# Schematic.net
KiCad netlist of a schematic drawn in Altium Designer
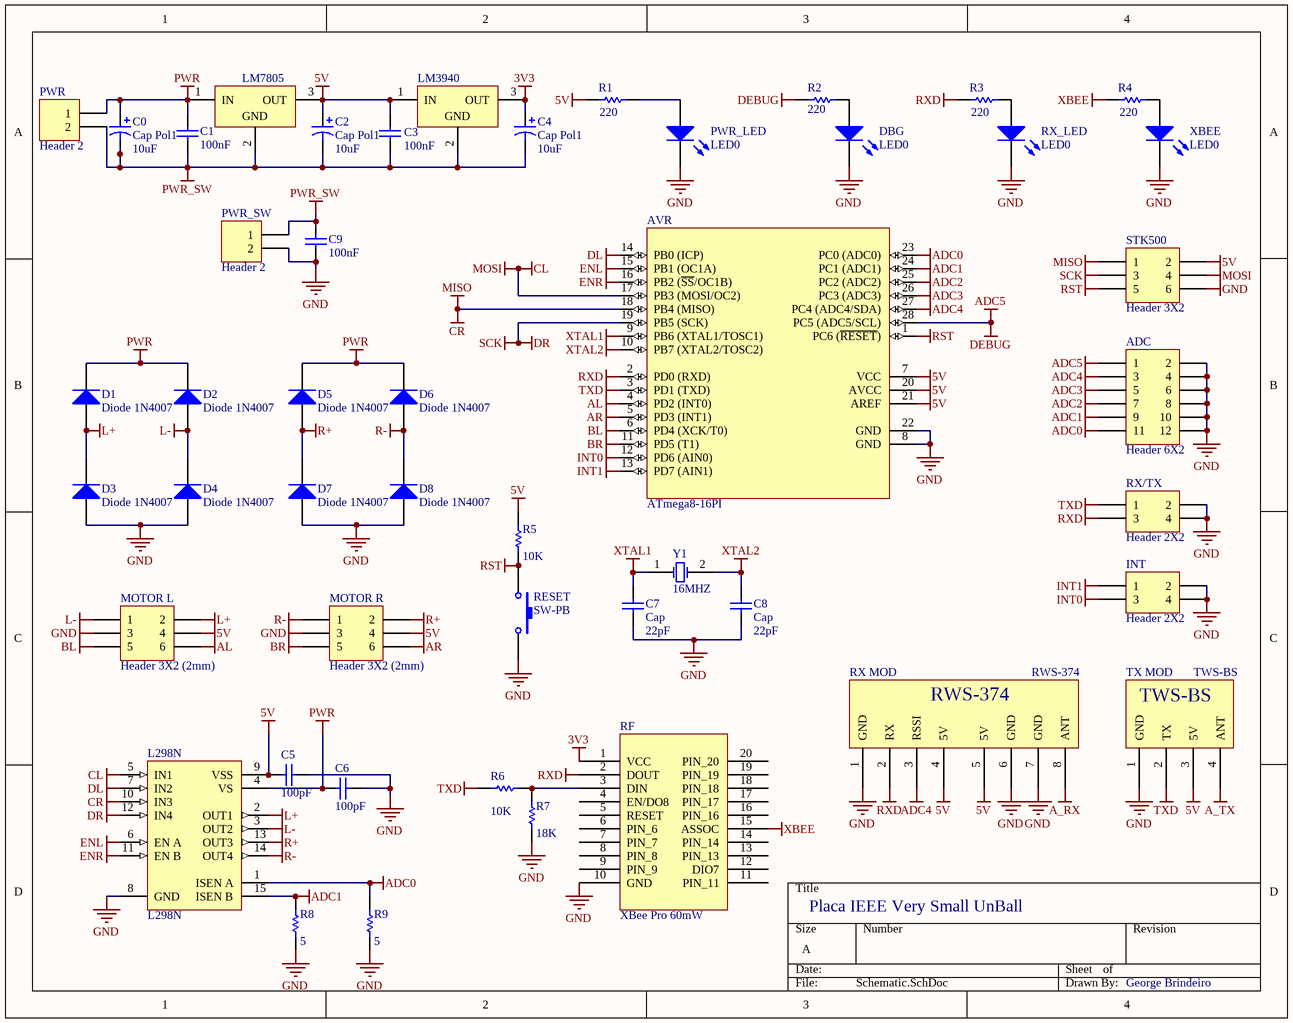
[diagram p0: Schematic.SchDoc]

(export (version "E")
  (design (tool "Eeschema 10.0.6"))
  (components
    (comp (ref "ADC")
      (value "Header 6X2")
      (footprint "HDR2X6")
      (description "Header, 6-Pin, Dual row")
      (fields (field (name "PUBLISHER") "Altium Limited"))
      (libsource (lib "Miscellaneous Connectors") (part "Header 6X2"))
    )
    (comp (ref "AVR")
      (value "ATmega8-16PI")
      (footprint "28P3")
      (description "8-Bit AVR Microcontroller with 8K Bytes of In-System Programmable Flash Memory")
      (fields (field (name "PUBLISHER") "Altium Limited"))
      (libsource (lib "Atmel Microcontroller 8-Bit AVR") (part "ATmega8-16PI"))
    )
    (comp (ref "C0")
      (value "Cap Pol1")
      (footprint "B")
      (description "Polarized Capacitor (Radial)")
      (fields (field (name "ALTIUM_VALUE") "10uF") (field (name "PUBLISHER") "Altium Limited"))
      (libsource (lib "Miscellaneous Devices") (part "Cap Pol1"))
    )
    (comp (ref "C1")
      (value "100nF")
      (footprint "C_NANO_HOLES")
      (description "Capacitor")
      (fields (field (name "Comment") "Cap") (field (name "PUBLISHER") "Altium Limited"))
      (libsource (lib "Miscellaneous Devices") (part "Cap"))
    )
    (comp (ref "C2")
      (value "Cap Pol1")
      (footprint "B")
      (description "Polarized Capacitor (Radial)")
      (fields (field (name "ALTIUM_VALUE") "10uF") (field (name "PUBLISHER") "Altium Limited"))
      (libsource (lib "Miscellaneous Devices") (part "Cap Pol1"))
    )
    (comp (ref "C3")
      (value "100nF")
      (footprint "C_NANO_HOLES")
      (description "Capacitor")
      (fields (field (name "Comment") "Cap") (field (name "PUBLISHER") "Altium Limited"))
      (libsource (lib "Miscellaneous Devices") (part "Cap"))
    )
    (comp (ref "C4")
      (value "Cap Pol1")
      (footprint "B")
      (description "Polarized Capacitor (Radial)")
      (fields (field (name "ALTIUM_VALUE") "10uF") (field (name "PUBLISHER") "Altium Limited"))
      (libsource (lib "Miscellaneous Devices") (part "Cap Pol1"))
    )
    (comp (ref "C5")
      (value "100pF")
      (footprint "C_NANO_HOLES")
      (description "Capacitor")
      (fields (field (name "Comment") "Cap") (field (name "PUBLISHER") "Altium Limited"))
      (libsource (lib "Miscellaneous Devices") (part "Cap"))
    )
    (comp (ref "C6")
      (value "100pF")
      (footprint "C_NANO_HOLES")
      (description "Capacitor")
      (fields (field (name "Comment") "Cap") (field (name "PUBLISHER") "Altium Limited"))
      (libsource (lib "Miscellaneous Devices") (part "Cap"))
    )
    (comp (ref "C7")
      (value "Cap")
      (footprint "C_NANO_HOLES")
      (description "Capacitor")
      (fields (field (name "ALTIUM_VALUE") "22pF") (field (name "PUBLISHER") "Altium Limited"))
      (libsource (lib "Miscellaneous Devices") (part "Cap"))
    )
    (comp (ref "C8")
      (value "Cap")
      (footprint "C_NANO_HOLES")
      (description "Capacitor")
      (fields (field (name "ALTIUM_VALUE") "22pF") (field (name "PUBLISHER") "Altium Limited"))
      (libsource (lib "Miscellaneous Devices") (part "Cap"))
    )
    (comp (ref "C9")
      (value "100nF")
      (footprint "C_NANO_HOLES")
      (description "Capacitor")
      (fields (field (name "Comment") "Cap") (field (name "PUBLISHER") "Altium Limited"))
      (libsource (lib "Miscellaneous Devices") (part "Cap"))
    )
    (comp (ref "D1")
      (value "Diode 1N4007")
      (footprint "DO-41")
      (description "1 Amp General Purpose Rectifier")
      (fields (field (name "PUBLISHER") "Altium Limited"))
      (libsource (lib "Miscellaneous Devices") (part "Diode 1N4007"))
    )
    (comp (ref "D2")
      (value "Diode 1N4007")
      (footprint "DO-41")
      (description "1 Amp General Purpose Rectifier")
      (fields (field (name "PUBLISHER") "Altium Limited"))
      (libsource (lib "Miscellaneous Devices") (part "Diode 1N4007"))
    )
    (comp (ref "D3")
      (value "Diode 1N4007")
      (footprint "DO-41")
      (description "1 Amp General Purpose Rectifier")
      (fields (field (name "PUBLISHER") "Altium Limited"))
      (libsource (lib "Miscellaneous Devices") (part "Diode 1N4007"))
    )
    (comp (ref "D4")
      (value "Diode 1N4007")
      (footprint "DO-41")
      (description "1 Amp General Purpose Rectifier")
      (fields (field (name "PUBLISHER") "Altium Limited"))
      (libsource (lib "Miscellaneous Devices") (part "Diode 1N4007"))
    )
    (comp (ref "D5")
      (value "Diode 1N4007")
      (footprint "DO-41")
      (description "1 Amp General Purpose Rectifier")
      (fields (field (name "PUBLISHER") "Altium Limited"))
      (libsource (lib "Miscellaneous Devices") (part "Diode 1N4007"))
    )
    (comp (ref "D6")
      (value "Diode 1N4007")
      (footprint "DO-41")
      (description "1 Amp General Purpose Rectifier")
      (fields (field (name "PUBLISHER") "Altium Limited"))
      (libsource (lib "Miscellaneous Devices") (part "Diode 1N4007"))
    )
    (comp (ref "D7")
      (value "Diode 1N4007")
      (footprint "DO-41")
      (description "1 Amp General Purpose Rectifier")
      (fields (field (name "PUBLISHER") "Altium Limited"))
      (libsource (lib "Miscellaneous Devices") (part "Diode 1N4007"))
    )
    (comp (ref "D8")
      (value "Diode 1N4007")
      (footprint "DO-41")
      (description "1 Amp General Purpose Rectifier")
      (fields (field (name "PUBLISHER") "Altium Limited"))
      (libsource (lib "Miscellaneous Devices") (part "Diode 1N4007"))
    )
    (comp (ref "DBG")
      (value "LED0")
      (footprint "B")
      (description "Typical INFRARED GaAs LED")
      (fields (field (name "PUBLISHER") "Altium Limited"))
      (libsource (lib "Miscellaneous Devices") (part "LED0"))
    )
    (comp (ref "INT")
      (value "Header 2X2")
      (footprint "HDR2X2")
      (description "Header, 2-Pin, Dual row")
      (fields (field (name "PUBLISHER") "Altium Limited"))
      (libsource (lib "Miscellaneous Connectors") (part "Header 2X2"))
    )
    (comp (ref "L298N")
      (value "L298N")
      (footprint "Multiwatt15V")
      (description "Dual Full Bridge Driver")
      (fields (field (name "PUBLISHER") "Altium Limited"))
      (libsource (lib "ST Interface DC Motor Controller") (part "L298N"))
    )
    (comp (ref "LM3940")
      (value "LM3940IT-3.3")
      (footprint "T03B")
      (description "1A Low Dropout Regulator for 5V to 3.3V Conversion")
      (fields
        (field (name "MANUFACTURER") "National Semiconductor")
        (field (name "DIGIKEYPARTNUMBER") "LM3940IT-3.3-ND")
        (field (name "PUBLISHER") "Altium Limited")
      )
      (libsource (lib "NSC LDO") (part "LM3940IT-3.3"))
    )
    (comp (ref "LM7805")
      (value "µA7805CKC")
      (footprint "KC03")
      (description "Positive-Voltage Regulator")
      (fields (field (name "PUBLISHER") "Altium Limited"))
      (libsource (lib "TI Power Mgt Voltage Regulator") (part "µA7805CKC"))
    )
    (comp (ref "MOTOR L")
      (value "Header 3X2 (2mm)")
      (footprint "HDR2x3_2MM")
      (description "Header, 3-Pin, Dual row")
      (fields (field (name "PUBLISHER") "Altium Limited"))
      (libsource (lib "Miscellaneous Connectors") (part "Header 3X2"))
    )
    (comp (ref "MOTOR R")
      (value "Header 3X2 (2mm)")
      (footprint "HDR2x3_2MM")
      (description "Header, 3-Pin, Dual row")
      (fields (field (name "PUBLISHER") "Altium Limited"))
      (libsource (lib "Miscellaneous Connectors") (part "Header 3X2"))
    )
    (comp (ref "PWR")
      (value "Header 2")
      (footprint "HDR1X2")
      (description "Header, 2-Pin")
      (fields (field (name "PUBLISHER") "Altium Limited"))
      (libsource (lib "Miscellaneous Connectors") (part "Header 2"))
    )
    (comp (ref "PWR_LED")
      (value "LED0")
      (footprint "B")
      (description "Typical INFRARED GaAs LED")
      (fields (field (name "PUBLISHER") "Altium Limited"))
      (libsource (lib "Miscellaneous Devices") (part "LED0"))
    )
    (comp (ref "PWR_SW")
      (value "Header 2")
      (footprint "HDR1X2")
      (description "Header, 2-Pin")
      (fields (field (name "PUBLISHER") "Altium Limited"))
      (libsource (lib "Miscellaneous Connectors") (part "Header 2"))
    )
    (comp (ref "R1")
      (value "220")
      (footprint "AXIAL-0.3")
      (description "Resistor")
      (fields (field (name "PUBLISHER") "Altium Limited"))
      (libsource (lib "Miscellaneous Devices") (part "Res1"))
    )
    (comp (ref "R2")
      (value "220")
      (footprint "AXIAL-0.3")
      (description "Resistor")
      (fields (field (name "PUBLISHER") "Altium Limited"))
      (libsource (lib "Miscellaneous Devices") (part "Res1"))
    )
    (comp (ref "R3")
      (value "220")
      (footprint "AXIAL-0.3")
      (description "Resistor")
      (fields (field (name "PUBLISHER") "Altium Limited"))
      (libsource (lib "Miscellaneous Devices") (part "Res1"))
    )
    (comp (ref "R4")
      (value "220")
      (footprint "AXIAL-0.3")
      (description "Resistor")
      (fields (field (name "PUBLISHER") "Altium Limited"))
      (libsource (lib "Miscellaneous Devices") (part "Res1"))
    )
    (comp (ref "R5")
      (value "10K")
      (footprint "AXIAL-0.3")
      (description "Resistor")
      (fields (field (name "PUBLISHER") "Altium Limited"))
      (libsource (lib "Miscellaneous Devices") (part "Res1"))
    )
    (comp (ref "R6")
      (value "10K")
      (footprint "AXIAL-0.3")
      (description "Resistor")
      (fields (field (name "PUBLISHER") "Altium Limited"))
      (libsource (lib "Miscellaneous Devices") (part "Res1"))
    )
    (comp (ref "R7")
      (value "18K")
      (footprint "AXIAL-0.3")
      (description "Resistor")
      (fields (field (name "PUBLISHER") "Altium Limited"))
      (libsource (lib "Miscellaneous Devices") (part "Res1"))
    )
    (comp (ref "R8")
      (value "5")
      (footprint "AXIAL-0.3")
      (description "Resistor")
      (fields (field (name "PUBLISHER") "Altium Limited"))
      (libsource (lib "Miscellaneous Devices") (part "Res1"))
    )
    (comp (ref "R9")
      (value "5")
      (footprint "AXIAL-0.3")
      (description "Resistor")
      (fields (field (name "PUBLISHER") "Altium Limited"))
      (libsource (lib "Miscellaneous Devices") (part "Res1"))
    )
    (comp (ref "RESET")
      (value "SW-PB")
      (footprint "PUSHBUTTON")
      (description "Switch")
      (fields (field (name "PUBLISHER") "Altium Limited"))
      (libsource (lib "Miscellaneous Devices") (part "SW-PB"))
    )
    (comp (ref "RF") (value "XBee Pro 60mW") (footprint "XBEE_PRO") (libsource (lib "Schlib") (part "XBee")))
    (comp (ref "RX MOD")
      (value "RWS-374")
      (footprint "RWS-374")
      (description "Receptor RF Soldafria")
      (libsource (lib "Schlib") (part "RWS-374"))
    )
    (comp (ref "RX/TX")
      (value "Header 2X2")
      (footprint "HDR2X2")
      (description "Header, 2-Pin, Dual row")
      (fields (field (name "PUBLISHER") "Altium Limited"))
      (libsource (lib "Miscellaneous Connectors") (part "Header 2X2"))
    )
    (comp (ref "RX_LED")
      (value "LED0")
      (footprint "B")
      (description "Typical INFRARED GaAs LED")
      (fields (field (name "PUBLISHER") "Altium Limited"))
      (libsource (lib "Miscellaneous Devices") (part "LED0"))
    )
    (comp (ref "STK500")
      (value "Header 3X2")
      (footprint "HDR2X3")
      (description "Header, 3-Pin, Dual row")
      (fields (field (name "PUBLISHER") "Altium Limited"))
      (libsource (lib "Miscellaneous Connectors") (part "Header 3X2"))
    )
    (comp (ref "TX MOD")
      (value "TWS-BS")
      (footprint "TWS-BS")
      (description "Transmissor RF Soldafria")
      (libsource (lib "Schlib") (part "TWS-BS"))
    )
    (comp (ref "XBEE")
      (value "LED0")
      (footprint "B")
      (description "Typical INFRARED GaAs LED")
      (fields (field (name "PUBLISHER") "Altium Limited"))
      (libsource (lib "Miscellaneous Devices") (part "LED0"))
    )
    (comp (ref "Y1")
      (value "16MHZ")
      (footprint "BCY-W2/E4.7")
      (description "Crystal Oscillator")
      (fields (field (name "PUBLISHER") "Altium Limited"))
      (libsource (lib "ECS Crystal Oscillator") (part "ECS-120-32-1"))
    )
  )
  (nets
    (net (code "1") (name "3V3") (class "Default")
      (node (ref "C4") (pin "1") (pinfunction "1_1") (pintype "passive"))
      (node (ref "LM3940") (pin "3") (pinfunction "OUT_3") (pintype "power_in"))
      (node (ref "RF") (pin "1") (pinfunction "VCC_1") (pintype "passive"))
    )
    (net (code "2") (name "5V") (class "Default")
      (node (ref "AVR") (pin "20") (pinfunction "AVCC_20") (pintype "power_in"))
      (node (ref "AVR") (pin "21") (pinfunction "AREF_21") (pintype "passive"))
      (node (ref "AVR") (pin "7") (pinfunction "VCC_7") (pintype "power_in"))
      (node (ref "C2") (pin "1") (pinfunction "1_1") (pintype "passive"))
      (node (ref "C3") (pin "1") (pinfunction "1_1") (pintype "passive"))
      (node (ref "C5") (pin "1") (pinfunction "1_1") (pintype "passive"))
      (node (ref "L298N") (pin "9") (pinfunction "VSS_9") (pintype "power_in"))
      (node (ref "LM3940") (pin "1") (pinfunction "IN_1") (pintype "power_in"))
      (node (ref "LM7805") (pin "3") (pinfunction "OUT_3") (pintype "power_in"))
      (node (ref "MOTOR L") (pin "4") (pinfunction "4_4") (pintype "passive"))
      (node (ref "MOTOR R") (pin "4") (pinfunction "4_4") (pintype "passive"))
      (node (ref "R1") (pin "1") (pinfunction "1_1") (pintype "passive"))
      (node (ref "R5") (pin "2") (pinfunction "2_2") (pintype "passive"))
      (node (ref "RX MOD") (pin "4") (pinfunction "5V_4") (pintype "passive"))
      (node (ref "RX MOD") (pin "5") (pinfunction "5V_5") (pintype "passive"))
      (node (ref "STK500") (pin "2") (pinfunction "2_2") (pintype "passive"))
      (node (ref "TX MOD") (pin "3") (pinfunction "5V_3") (pintype "passive"))
    )
    (net (code "3") (name "ADC0") (class "Default")
      (node (ref "ADC") (pin "11") (pinfunction "11_11") (pintype "passive"))
      (node (ref "AVR") (pin "23") (pinfunction "PC0_(ADC0)_23") (pintype "bidirectional"))
      (node (ref "L298N") (pin "1") (pinfunction "ISEN_A_1") (pintype "passive"))
      (node (ref "R9") (pin "2") (pinfunction "2_2") (pintype "passive"))
    )
    (net (code "4") (name "ADC1") (class "Default")
      (node (ref "ADC") (pin "9") (pinfunction "9_9") (pintype "passive"))
      (node (ref "AVR") (pin "24") (pinfunction "PC1_(ADC1)_24") (pintype "bidirectional"))
      (node (ref "L298N") (pin "15") (pinfunction "ISEN_B_15") (pintype "passive"))
      (node (ref "R8") (pin "2") (pinfunction "2_2") (pintype "passive"))
    )
    (net (code "5") (name "ADC2") (class "Default")
      (node (ref "ADC") (pin "7") (pinfunction "7_7") (pintype "passive"))
      (node (ref "AVR") (pin "25") (pinfunction "PC2_(ADC2)_25") (pintype "bidirectional"))
    )
    (net (code "6") (name "ADC3") (class "Default")
      (node (ref "ADC") (pin "5") (pinfunction "5_5") (pintype "passive"))
      (node (ref "AVR") (pin "26") (pinfunction "PC3_(ADC3)_26") (pintype "bidirectional"))
    )
    (net (code "7") (name "ADC4") (class "Default")
      (node (ref "ADC") (pin "3") (pinfunction "3_3") (pintype "passive"))
      (node (ref "AVR") (pin "27") (pinfunction "PC4_(ADC4/SDA)_27") (pintype "bidirectional"))
      (node (ref "RX MOD") (pin "3") (pinfunction "RSSI_3") (pintype "passive"))
    )
    (net (code "8") (name "ADC5") (class "Default")
      (node (ref "ADC") (pin "1") (pinfunction "1_1") (pintype "passive"))
      (node (ref "AVR") (pin "28") (pinfunction "PC5_(ADC5/SCL)_28") (pintype "bidirectional"))
      (node (ref "R2") (pin "1") (pinfunction "1_1") (pintype "passive"))
    )
    (net (code "9") (name "AL") (class "Default")
      (node (ref "AVR") (pin "4") (pinfunction "PD2_(INT0)_4") (pintype "bidirectional"))
      (node (ref "MOTOR L") (pin "6") (pinfunction "6_6") (pintype "passive"))
    )
    (net (code "10") (name "AR") (class "Default")
      (node (ref "AVR") (pin "5") (pinfunction "PD3_(INT1)_5") (pintype "bidirectional"))
      (node (ref "MOTOR R") (pin "6") (pinfunction "6_6") (pintype "passive"))
    )
    (net (code "11") (name "A_RX") (class "Default")
      (node (ref "RX MOD") (pin "8") (pinfunction "ANT_8") (pintype "passive"))
    )
    (net (code "12") (name "A_TX") (class "Default")
      (node (ref "TX MOD") (pin "4") (pinfunction "ANT_4") (pintype "passive"))
    )
    (net (code "13") (name "BL") (class "Default")
      (node (ref "AVR") (pin "6") (pinfunction "PD4_(XCK/T0)_6") (pintype "bidirectional"))
      (node (ref "MOTOR L") (pin "5") (pinfunction "5_5") (pintype "passive"))
    )
    (net (code "14") (name "BR") (class "Default")
      (node (ref "AVR") (pin "11") (pinfunction "PD5_(T1)_11") (pintype "bidirectional"))
      (node (ref "MOTOR R") (pin "5") (pinfunction "5_5") (pintype "passive"))
    )
    (net (code "15") (name "CL") (class "Default")
      (node (ref "AVR") (pin "17") (pinfunction "PB3_(MOSI/OC2)_17") (pintype "bidirectional"))
      (node (ref "L298N") (pin "5") (pinfunction "IN1_5") (pintype "input"))
      (node (ref "STK500") (pin "4") (pinfunction "4_4") (pintype "passive"))
    )
    (net (code "16") (name "CR") (class "Default")
      (node (ref "AVR") (pin "18") (pinfunction "PB4_(MISO)_18") (pintype "bidirectional"))
      (node (ref "L298N") (pin "10") (pinfunction "IN3_10") (pintype "input"))
      (node (ref "STK500") (pin "1") (pinfunction "1_1") (pintype "passive"))
    )
    (net (code "17") (name "DL") (class "Default")
      (node (ref "AVR") (pin "14") (pinfunction "PB0_(ICP)_14") (pintype "bidirectional"))
      (node (ref "L298N") (pin "7") (pinfunction "IN2_7") (pintype "input"))
    )
    (net (code "18") (name "DR") (class "Default")
      (node (ref "AVR") (pin "19") (pinfunction "PB5_(SCK)_19") (pintype "bidirectional"))
      (node (ref "L298N") (pin "12") (pinfunction "IN4_12") (pintype "input"))
      (node (ref "STK500") (pin "3") (pinfunction "3_3") (pintype "passive"))
    )
    (net (code "19") (name "ENL") (class "Default")
      (node (ref "AVR") (pin "15") (pinfunction "PB1_(OC1A)_15") (pintype "bidirectional"))
      (node (ref "L298N") (pin "6") (pinfunction "EN_A_6") (pintype "input"))
    )
    (net (code "20") (name "ENR") (class "Default")
      (node (ref "AVR") (pin "16") (pinfunction "PB2_(~{SS}/OC1B)_16") (pintype "bidirectional"))
      (node (ref "L298N") (pin "11") (pinfunction "EN_B_11") (pintype "input"))
    )
    (net (code "21") (name "GND") (class "Default")
      (node (ref "ADC") (pin "10") (pinfunction "10_10") (pintype "passive"))
      (node (ref "ADC") (pin "12") (pinfunction "12_12") (pintype "passive"))
      (node (ref "ADC") (pin "2") (pinfunction "2_2") (pintype "passive"))
      (node (ref "ADC") (pin "4") (pinfunction "4_4") (pintype "passive"))
      (node (ref "ADC") (pin "6") (pinfunction "6_6") (pintype "passive"))
      (node (ref "ADC") (pin "8") (pinfunction "8_8") (pintype "passive"))
      (node (ref "AVR") (pin "22") (pinfunction "GND_22") (pintype "power_in"))
      (node (ref "AVR") (pin "8") (pinfunction "GND_8") (pintype "power_in"))
      (node (ref "C5") (pin "2") (pinfunction "2_2") (pintype "passive"))
      (node (ref "C6") (pin "2") (pinfunction "2_2") (pintype "passive"))
      (node (ref "C7") (pin "2") (pinfunction "2_2") (pintype "passive"))
      (node (ref "C8") (pin "2") (pinfunction "2_2") (pintype "passive"))
      (node (ref "C9") (pin "2") (pinfunction "2_2") (pintype "passive"))
      (node (ref "D3") (pin "1") (pinfunction "A_1") (pintype "passive"))
      (node (ref "D4") (pin "1") (pinfunction "A_1") (pintype "passive"))
      (node (ref "D7") (pin "1") (pinfunction "A_1") (pintype "passive"))
      (node (ref "D8") (pin "1") (pinfunction "A_1") (pintype "passive"))
      (node (ref "DBG") (pin "2") (pinfunction "K_2") (pintype "passive"))
      (node (ref "INT") (pin "2") (pinfunction "2_2") (pintype "passive"))
      (node (ref "INT") (pin "4") (pinfunction "4_4") (pintype "passive"))
      (node (ref "L298N") (pin "8") (pinfunction "GND_8") (pintype "power_in"))
      (node (ref "MOTOR L") (pin "3") (pinfunction "3_3") (pintype "passive"))
      (node (ref "MOTOR R") (pin "3") (pinfunction "3_3") (pintype "passive"))
      (node (ref "PWR_LED") (pin "2") (pinfunction "K_2") (pintype "passive"))
      (node (ref "PWR_SW") (pin "2") (pinfunction "2_2") (pintype "passive"))
      (node (ref "R7") (pin "2") (pinfunction "2_2") (pintype "passive"))
      (node (ref "R8") (pin "1") (pinfunction "1_1") (pintype "passive"))
      (node (ref "R9") (pin "1") (pinfunction "1_1") (pintype "passive"))
      (node (ref "RESET") (pin "2") (pinfunction "2_2") (pintype "passive"))
      (node (ref "RF") (pin "10") (pinfunction "GND_10") (pintype "passive"))
      (node (ref "RX MOD") (pin "1") (pinfunction "GND_1") (pintype "passive"))
      (node (ref "RX MOD") (pin "6") (pinfunction "GND_6") (pintype "passive"))
      (node (ref "RX MOD") (pin "7") (pinfunction "GND_7") (pintype "passive"))
      (node (ref "RX/TX") (pin "2") (pinfunction "2_2") (pintype "passive"))
      (node (ref "RX/TX") (pin "4") (pinfunction "4_4") (pintype "passive"))
      (node (ref "RX_LED") (pin "2") (pinfunction "K_2") (pintype "passive"))
      (node (ref "STK500") (pin "6") (pinfunction "6_6") (pintype "passive"))
      (node (ref "TX MOD") (pin "1") (pinfunction "GND_1") (pintype "passive"))
      (node (ref "XBEE") (pin "2") (pinfunction "K_2") (pintype "passive"))
    )
    (net (code "22") (name "INT0") (class "Default")
      (node (ref "AVR") (pin "12") (pinfunction "PD6_(AIN0)_12") (pintype "bidirectional"))
      (node (ref "INT") (pin "3") (pinfunction "3_3") (pintype "passive"))
    )
    (net (code "23") (name "INT1") (class "Default")
      (node (ref "AVR") (pin "13") (pinfunction "PD7_(AIN1)_13") (pintype "bidirectional"))
      (node (ref "INT") (pin "1") (pinfunction "1_1") (pintype "passive"))
    )
    (net (code "24") (name "L+") (class "Default")
      (node (ref "D1") (pin "1") (pinfunction "A_1") (pintype "passive"))
      (node (ref "D3") (pin "2") (pinfunction "K_2") (pintype "passive"))
      (node (ref "L298N") (pin "2") (pinfunction "OUT1_2") (pintype "output"))
      (node (ref "MOTOR L") (pin "2") (pinfunction "2_2") (pintype "passive"))
    )
    (net (code "25") (name "L-") (class "Default")
      (node (ref "D2") (pin "1") (pinfunction "A_1") (pintype "passive"))
      (node (ref "D4") (pin "2") (pinfunction "K_2") (pintype "passive"))
      (node (ref "L298N") (pin "3") (pinfunction "OUT2_3") (pintype "output"))
      (node (ref "MOTOR L") (pin "1") (pinfunction "1_1") (pintype "passive"))
    )
    (net (code "26") (name "Net-(DBG-A)") (class "Default")
      (node (ref "DBG") (pin "1") (pinfunction "A_1") (pintype "passive"))
      (node (ref "R2") (pin "2") (pinfunction "2_2") (pintype "passive"))
    )
    (net (code "27") (name "Net-(PWR_LED-A)") (class "Default")
      (node (ref "PWR_LED") (pin "1") (pinfunction "A_1") (pintype "passive"))
      (node (ref "R1") (pin "2") (pinfunction "2_2") (pintype "passive"))
    )
    (net (code "28") (name "Net-(RF-DIN)") (class "Default")
      (node (ref "R6") (pin "1") (pinfunction "1_1") (pintype "passive"))
      (node (ref "R7") (pin "1") (pinfunction "1_1") (pintype "passive"))
      (node (ref "RF") (pin "3") (pinfunction "DIN_3") (pintype "passive"))
    )
    (net (code "29") (name "Net-(RX_LED-A)") (class "Default")
      (node (ref "R3") (pin "2") (pinfunction "2_2") (pintype "passive"))
      (node (ref "RX_LED") (pin "1") (pinfunction "A_1") (pintype "passive"))
    )
    (net (code "30") (name "Net-(XBEE-A)") (class "Default")
      (node (ref "R4") (pin "2") (pinfunction "2_2") (pintype "passive"))
      (node (ref "XBEE") (pin "1") (pinfunction "A_1") (pintype "passive"))
    )
    (net (code "31") (name "PWR") (class "Default")
      (node (ref "C0") (pin "1") (pinfunction "1_1") (pintype "passive"))
      (node (ref "C1") (pin "1") (pinfunction "1_1") (pintype "passive"))
      (node (ref "C6") (pin "1") (pinfunction "1_1") (pintype "passive"))
      (node (ref "D1") (pin "2") (pinfunction "K_2") (pintype "passive"))
      (node (ref "D2") (pin "2") (pinfunction "K_2") (pintype "passive"))
      (node (ref "D5") (pin "2") (pinfunction "K_2") (pintype "passive"))
      (node (ref "D6") (pin "2") (pinfunction "K_2") (pintype "passive"))
      (node (ref "L298N") (pin "4") (pinfunction "VS_4") (pintype "power_in"))
      (node (ref "LM7805") (pin "1") (pinfunction "IN_1") (pintype "power_in"))
      (node (ref "PWR") (pin "1") (pinfunction "1_1") (pintype "passive"))
    )
    (net (code "32") (name "PWR_SW") (class "Default")
      (node (ref "C0") (pin "2") (pinfunction "2_2") (pintype "passive"))
      (node (ref "C1") (pin "2") (pinfunction "2_2") (pintype "passive"))
      (node (ref "C2") (pin "2") (pinfunction "2_2") (pintype "passive"))
      (node (ref "C3") (pin "2") (pinfunction "2_2") (pintype "passive"))
      (node (ref "C4") (pin "2") (pinfunction "2_2") (pintype "passive"))
      (node (ref "C9") (pin "1") (pinfunction "1_1") (pintype "passive"))
      (node (ref "LM3940") (pin "2") (pinfunction "GND_2") (pintype "power_in"))
      (node (ref "LM7805") (pin "2") (pinfunction "GND_2") (pintype "power_in"))
      (node (ref "PWR") (pin "2") (pinfunction "2_2") (pintype "passive"))
      (node (ref "PWR_SW") (pin "1") (pinfunction "1_1") (pintype "passive"))
    )
    (net (code "33") (name "R+") (class "Default")
      (node (ref "D5") (pin "1") (pinfunction "A_1") (pintype "passive"))
      (node (ref "D7") (pin "2") (pinfunction "K_2") (pintype "passive"))
      (node (ref "L298N") (pin "13") (pinfunction "OUT3_13") (pintype "output"))
      (node (ref "MOTOR R") (pin "2") (pinfunction "2_2") (pintype "passive"))
    )
    (net (code "34") (name "R-") (class "Default")
      (node (ref "D6") (pin "1") (pinfunction "A_1") (pintype "passive"))
      (node (ref "D8") (pin "2") (pinfunction "K_2") (pintype "passive"))
      (node (ref "L298N") (pin "14") (pinfunction "OUT4_14") (pintype "output"))
      (node (ref "MOTOR R") (pin "1") (pinfunction "1_1") (pintype "passive"))
    )
    (net (code "35") (name "RST") (class "Default")
      (node (ref "AVR") (pin "1") (pinfunction "PC6_(~{RESET})_1") (pintype "bidirectional"))
      (node (ref "R5") (pin "1") (pinfunction "1_1") (pintype "passive"))
      (node (ref "RESET") (pin "1") (pinfunction "1_1") (pintype "passive"))
      (node (ref "STK500") (pin "5") (pinfunction "5_5") (pintype "passive"))
    )
    (net (code "36") (name "RXD") (class "Default")
      (node (ref "AVR") (pin "2") (pinfunction "PD0_(RXD)_2") (pintype "bidirectional"))
      (node (ref "R3") (pin "1") (pinfunction "1_1") (pintype "passive"))
      (node (ref "RF") (pin "2") (pinfunction "DOUT_2") (pintype "passive"))
      (node (ref "RX MOD") (pin "2") (pinfunction "RX_2") (pintype "passive"))
      (node (ref "RX/TX") (pin "3") (pinfunction "3_3") (pintype "passive"))
    )
    (net (code "37") (name "TXD") (class "Default")
      (node (ref "AVR") (pin "3") (pinfunction "PD1_(TXD)_3") (pintype "bidirectional"))
      (node (ref "R6") (pin "2") (pinfunction "2_2") (pintype "passive"))
      (node (ref "RX/TX") (pin "1") (pinfunction "1_1") (pintype "passive"))
      (node (ref "TX MOD") (pin "2") (pinfunction "TX_2") (pintype "passive"))
    )
    (net (code "38") (name "XBEE") (class "Default")
      (node (ref "R4") (pin "1") (pinfunction "1_1") (pintype "passive"))
      (node (ref "RF") (pin "15") (pinfunction "ASSOC_15") (pintype "passive"))
    )
    (net (code "39") (name "XTAL1") (class "Default")
      (node (ref "AVR") (pin "9") (pinfunction "PB6_(XTAL1/TOSC1)_9") (pintype "bidirectional"))
      (node (ref "C7") (pin "1") (pinfunction "1_1") (pintype "passive"))
      (node (ref "Y1") (pin "1") (pinfunction "OSC1_1") (pintype "passive"))
    )
    (net (code "40") (name "XTAL2") (class "Default")
      (node (ref "AVR") (pin "10") (pinfunction "PB7_(XTAL2/TOSC2)_10") (pintype "bidirectional"))
      (node (ref "C8") (pin "1") (pinfunction "1_1") (pintype "passive"))
      (node (ref "Y1") (pin "2") (pinfunction "OSC2_2") (pintype "passive"))
    )
    (net (code "41") (name "unconnected-(RF-DIO7-Pad12)") (class "Default")
      (node (ref "RF") (pin "12") (pinfunction "DIO7_12") (pintype "passive"))
    )
    (net (code "42") (name "unconnected-(RF-EN{slash}DO8-Pad4)") (class "Default")
      (node (ref "RF") (pin "4") (pinfunction "EN/DO8_4") (pintype "passive"))
    )
    (net (code "43") (name "unconnected-(RF-PIN_6-Pad6)") (class "Default")
      (node (ref "RF") (pin "6") (pinfunction "PIN_6_6") (pintype "passive"))
    )
    (net (code "44") (name "unconnected-(RF-PIN_7-Pad7)") (class "Default")
      (node (ref "RF") (pin "7") (pinfunction "PIN_7_7") (pintype "passive"))
    )
    (net (code "45") (name "unconnected-(RF-PIN_8-Pad8)") (class "Default")
      (node (ref "RF") (pin "8") (pinfunction "PIN_8_8") (pintype "passive"))
    )
    (net (code "46") (name "unconnected-(RF-PIN_9-Pad9)") (class "Default")
      (node (ref "RF") (pin "9") (pinfunction "PIN_9_9") (pintype "passive"))
    )
    (net (code "47") (name "unconnected-(RF-PIN_11-Pad11)") (class "Default")
      (node (ref "RF") (pin "11") (pinfunction "PIN_11_11") (pintype "passive"))
    )
    (net (code "48") (name "unconnected-(RF-PIN_13-Pad13)") (class "Default")
      (node (ref "RF") (pin "13") (pinfunction "PIN_13_13") (pintype "passive"))
    )
    (net (code "49") (name "unconnected-(RF-PIN_14-Pad14)") (class "Default")
      (node (ref "RF") (pin "14") (pinfunction "PIN_14_14") (pintype "passive"))
    )
    (net (code "50") (name "unconnected-(RF-PIN_16-Pad16)") (class "Default")
      (node (ref "RF") (pin "16") (pinfunction "PIN_16_16") (pintype "passive"))
    )
    (net (code "51") (name "unconnected-(RF-PIN_17-Pad17)") (class "Default")
      (node (ref "RF") (pin "17") (pinfunction "PIN_17_17") (pintype "passive"))
    )
    (net (code "52") (name "unconnected-(RF-PIN_18-Pad18)") (class "Default")
      (node (ref "RF") (pin "18") (pinfunction "PIN_18_18") (pintype "passive"))
    )
    (net (code "53") (name "unconnected-(RF-PIN_19-Pad19)") (class "Default")
      (node (ref "RF") (pin "19") (pinfunction "PIN_19_19") (pintype "passive"))
    )
    (net (code "54") (name "unconnected-(RF-PIN_20-Pad20)") (class "Default")
      (node (ref "RF") (pin "20") (pinfunction "PIN_20_20") (pintype "passive"))
    )
    (net (code "55") (name "unconnected-(RF-RESET-Pad5)") (class "Default")
      (node (ref "RF") (pin "5") (pinfunction "RESET_5") (pintype "passive"))
    )
  )
)
